# projekt.net
KiCad netlist of a schematic drawn in EAGLE
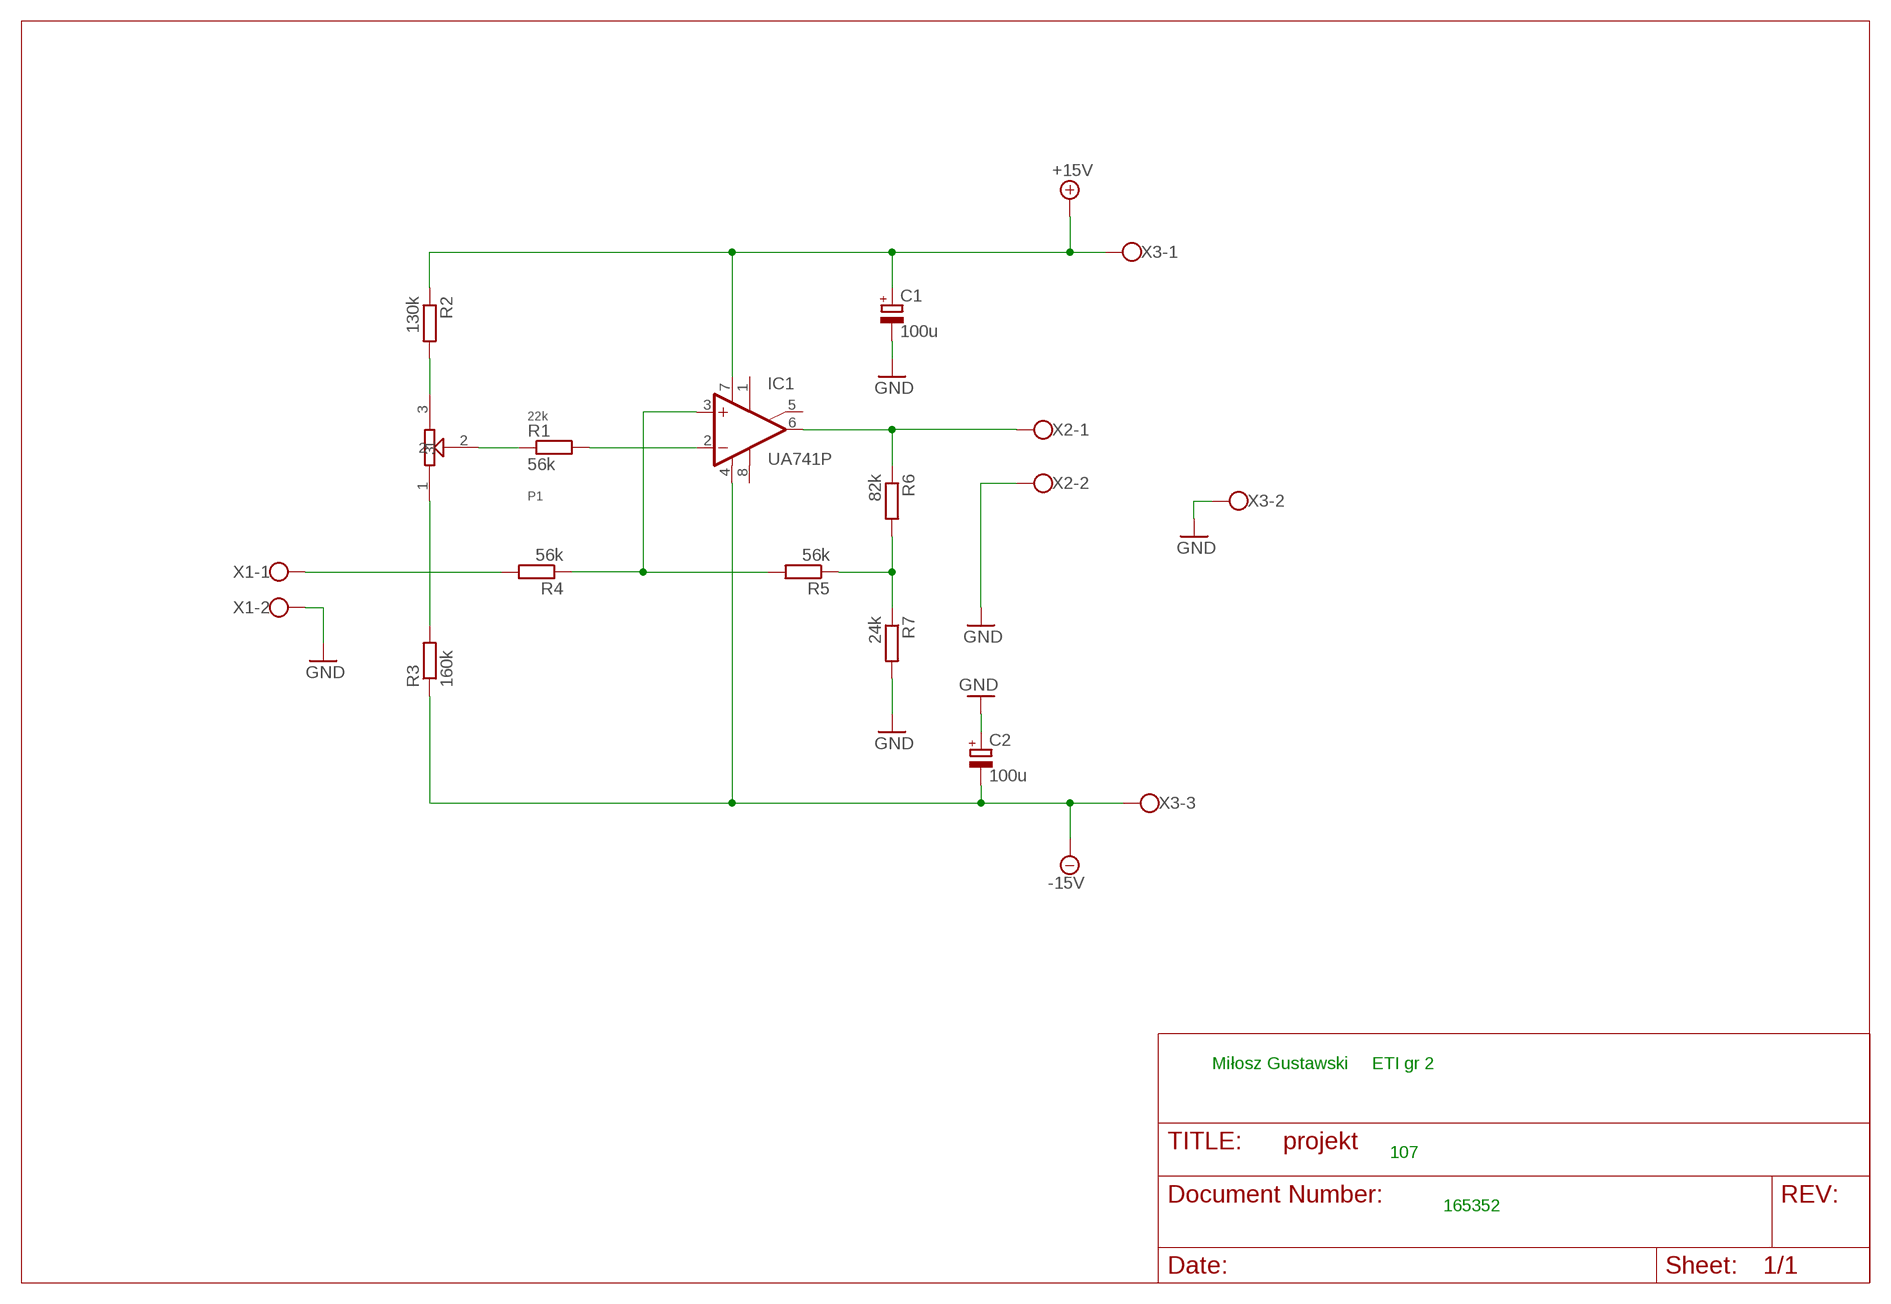
[diagram p0: schematic, sheet 1]

(export (version "E")
  (design (tool "Eeschema 10.0.6"))
  (components
    (comp (ref "C1")
      (value "100u")
      (footprint "eagle-import:140CLH-1014")
      (libsource (lib "eagle-import") (part "CPOL-EU140CLH-1014"))
    )
    (comp (ref "C2")
      (value "100u")
      (footprint "eagle-import:140CLH-1014")
      (libsource (lib "eagle-import") (part "CPOL-EU140CLH-1014"))
    )
    (comp (ref "IC1")
      (value "UA741P")
      (footprint "eagle-import:DIL08")
      (libsource (lib "eagle-import") (part "741PUA"))
    )
    (comp (ref "P1")
      (value "22k")
      (footprint "eagle-import:CN15.2")
      (libsource (lib "eagle-import") (part "POTENCJOMETR"))
    )
    (comp (ref "R1")
      (value "56k")
      (footprint "eagle-import:0207_10")
      (libsource (lib "eagle-import") (part "R-EU_0207/10"))
    )
    (comp (ref "R2")
      (value "130k")
      (footprint "eagle-import:0207_10")
      (libsource (lib "eagle-import") (part "R-EU_0207/10"))
    )
    (comp (ref "R3")
      (value "160k")
      (footprint "eagle-import:0207_10")
      (libsource (lib "eagle-import") (part "R-EU_0207/10"))
    )
    (comp (ref "R4")
      (value "56k")
      (footprint "eagle-import:0207_10")
      (libsource (lib "eagle-import") (part "R-EU_0207/10"))
    )
    (comp (ref "R5")
      (value "56k")
      (footprint "eagle-import:0207_10")
      (libsource (lib "eagle-import") (part "R-EU_0207/10"))
    )
    (comp (ref "R6")
      (value "82k")
      (footprint "eagle-import:0207_10")
      (libsource (lib "eagle-import") (part "R-EU_0207/10"))
    )
    (comp (ref "R7")
      (value "24k")
      (footprint "eagle-import:0207_10")
      (libsource (lib "eagle-import") (part "R-EU_0207/10"))
    )
    (comp (ref "X1")
      (value "W237-102")
      (footprint "eagle-import:W237-102")
      (fields (field (name "MPN") "237-102"))
      (libsource (lib "eagle-import") (part "W237-102"))
    )
    (comp (ref "X2")
      (value "W237-102")
      (footprint "eagle-import:W237-102")
      (fields (field (name "MPN") "237-102"))
      (libsource (lib "eagle-import") (part "W237-102"))
    )
    (comp (ref "X3")
      (value "W237-103")
      (footprint "eagle-import:W237-103")
      (fields (field (name "MPN") "237-103"))
      (libsource (lib "eagle-import") (part "W237-103"))
    )
  )
  (nets
    (net (code "1") (name "+15V") (class "Default")
      (node (ref "C1") (pin "+") (pinfunction "+_+") (pintype "passive"))
      (node (ref "IC1") (pin "7") (pinfunction "V+_7") (pintype "power_in"))
      (node (ref "R2") (pin "1") (pinfunction "1_1") (pintype "passive"))
      (node (ref "X3") (pin "1") (pinfunction "KL_1") (pintype "passive"))
    )
    (net (code "2") (name "-15V") (class "Default")
      (node (ref "C2") (pin "-") (pinfunction "-_-") (pintype "passive"))
      (node (ref "IC1") (pin "4") (pinfunction "V-_4") (pintype "power_in"))
      (node (ref "R3") (pin "1") (pinfunction "1_1") (pintype "passive"))
      (node (ref "X3") (pin "3") (pinfunction "KL_3") (pintype "passive"))
    )
    (net (code "3") (name "GND") (class "Default")
      (node (ref "C1") (pin "-") (pinfunction "-_-") (pintype "passive"))
      (node (ref "C2") (pin "+") (pinfunction "+_+") (pintype "passive"))
      (node (ref "R7") (pin "2") (pinfunction "2_2") (pintype "passive"))
      (node (ref "X1") (pin "2") (pinfunction "KL_2") (pintype "passive"))
      (node (ref "X2") (pin "2") (pinfunction "KL_2") (pintype "passive"))
      (node (ref "X3") (pin "2") (pinfunction "KL_2") (pintype "passive"))
    )
    (net (code "4") (name "Net-(IC1-+IN)") (class "Default")
      (node (ref "IC1") (pin "3") (pinfunction "+IN_3") (pintype "input"))
      (node (ref "R4") (pin "1") (pinfunction "1_1") (pintype "passive"))
      (node (ref "R5") (pin "2") (pinfunction "2_2") (pintype "passive"))
    )
    (net (code "5") (name "Net-(IC1--IN)") (class "Default")
      (node (ref "IC1") (pin "2") (pinfunction "-IN_2") (pintype "input"))
      (node (ref "R1") (pin "2") (pinfunction "2_2") (pintype "passive"))
    )
    (net (code "6") (name "Net-(IC1-OUT)") (class "Default")
      (node (ref "IC1") (pin "6") (pinfunction "OUT_6") (pintype "output"))
      (node (ref "R6") (pin "1") (pinfunction "1_1") (pintype "passive"))
      (node (ref "X2") (pin "1") (pinfunction "KL_1") (pintype "passive"))
    )
    (net (code "7") (name "Net-(P1-Pad1)") (class "Default")
      (node (ref "P1") (pin "1") (pinfunction "1_1") (pintype "bidirectional"))
      (node (ref "R3") (pin "2") (pinfunction "2_2") (pintype "passive"))
    )
    (net (code "8") (name "Net-(P1-Pad2)") (class "Default")
      (node (ref "P1") (pin "2") (pinfunction "2_2") (pintype "bidirectional"))
      (node (ref "R1") (pin "1") (pinfunction "1_1") (pintype "passive"))
    )
    (net (code "9") (name "Net-(P1-Pad3)") (class "Default")
      (node (ref "P1") (pin "3") (pinfunction "3_3") (pintype "bidirectional"))
      (node (ref "R2") (pin "2") (pinfunction "2_2") (pintype "passive"))
    )
    (net (code "10") (name "Net-(R5-Pad1)") (class "Default")
      (node (ref "R5") (pin "1") (pinfunction "1_1") (pintype "passive"))
      (node (ref "R6") (pin "2") (pinfunction "2_2") (pintype "passive"))
      (node (ref "R7") (pin "1") (pinfunction "1_1") (pintype "passive"))
    )
    (net (code "11") (name "Net-(X1A-KL)") (class "Default")
      (node (ref "R4") (pin "2") (pinfunction "2_2") (pintype "passive"))
      (node (ref "X1") (pin "1") (pinfunction "KL_1") (pintype "passive"))
    )
    (net (code "12") (name "unconnected-(IC1-ON1-Pad1)") (class "Default")
      (node (ref "IC1") (pin "1") (pinfunction "ON1_1") (pintype "passive"))
    )
    (net (code "13") (name "unconnected-(IC1-ON2-Pad5)") (class "Default")
      (node (ref "IC1") (pin "5") (pinfunction "ON2_5") (pintype "passive"))
    )
    (net (code "14") (name "unconnected-(IC1-OPT-Pad8)") (class "Default")
      (node (ref "IC1") (pin "8") (pinfunction "OPT_8") (pintype "passive"))
    )
  )
)
